# Sheet1.net
KiCad netlist of a schematic drawn in Altium Designer
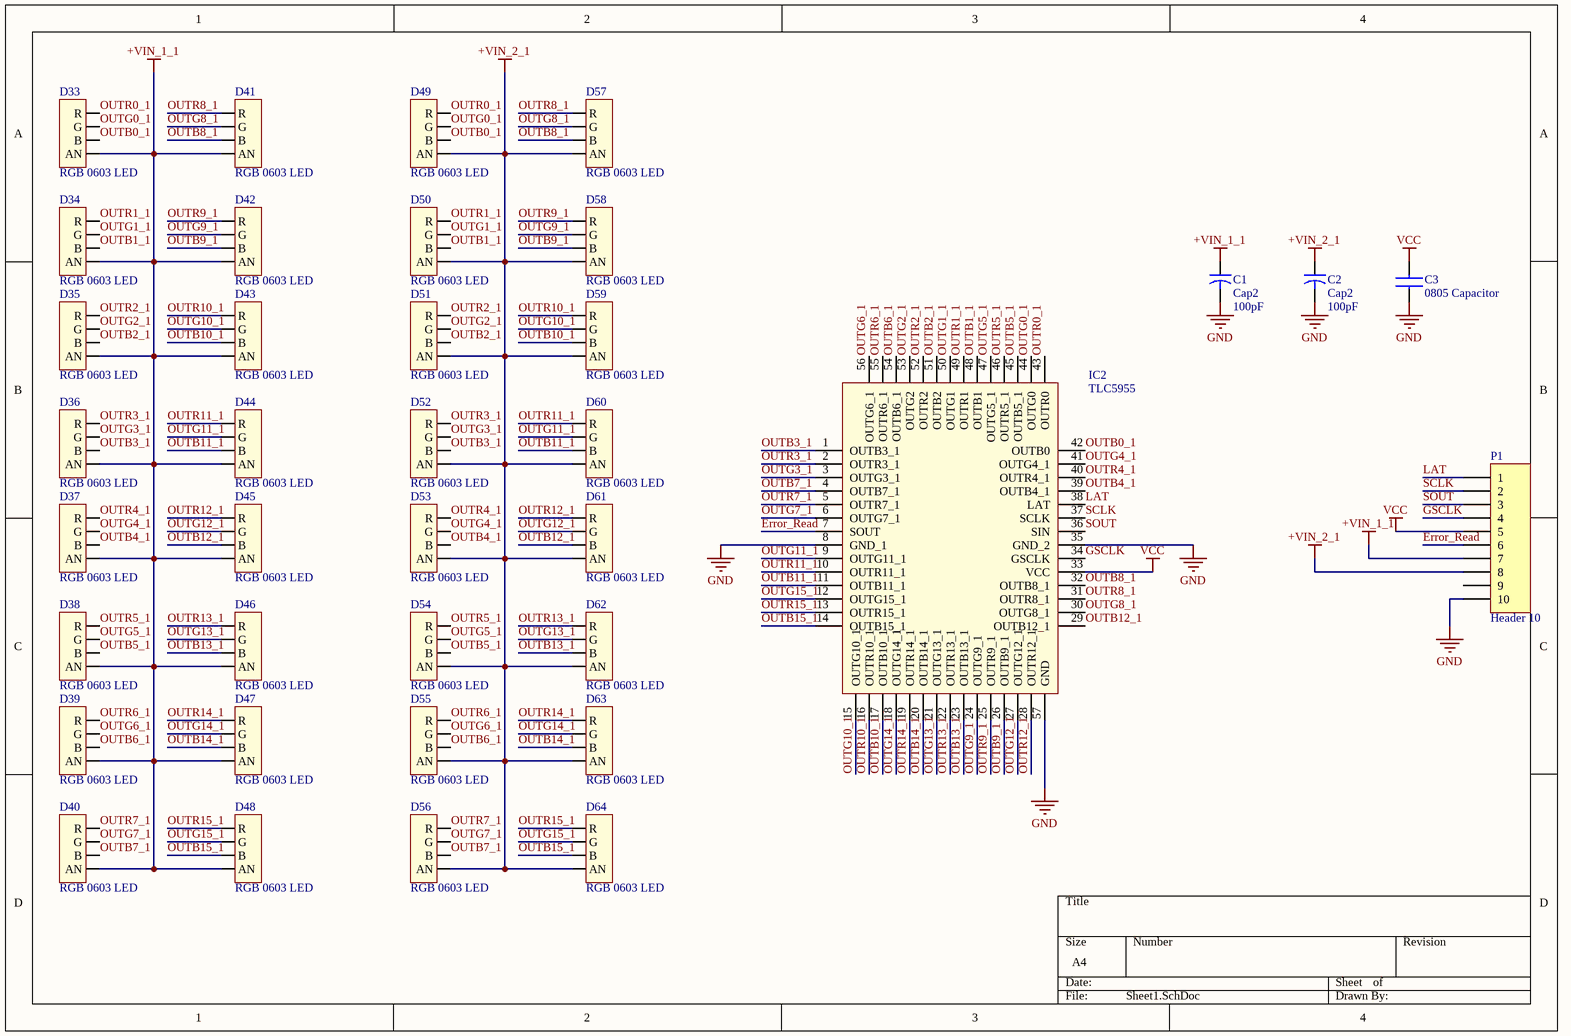
[diagram p0: Sheet1.SchDoc]

(export (version "E")
  (design (tool "Eeschema 10.0.6"))
  (components
    (comp (ref "C1")
      (value "Cap2")
      (footprint "CAPR5-4X5")
      (description "Capacitor")
      (fields (field (name "ALTIUM_VALUE") "100pF") (field (name "PUBLISHER") "Altium Limited"))
      (libsource (lib "Miscellaneous Devices") (part "Cap2"))
    )
    (comp (ref "C2")
      (value "Cap2")
      (footprint "CAPR5-4X5")
      (description "Capacitor")
      (fields (field (name "ALTIUM_VALUE") "100pF") (field (name "PUBLISHER") "Altium Limited"))
      (libsource (lib "Miscellaneous Devices") (part "Cap2"))
    )
    (comp (ref "C3")
      (value "0805 Capacitor")
      (footprint "0805 Capacitor")
      (libsource (lib "Schlib1") (part "0805 Capacitor"))
    )
    (comp (ref "D33")
      (value "RGB 0603 LED")
      (footprint "RGB LED")
      (libsource (lib "Schlib1") (part "RGB 0603 LED"))
    )
    (comp (ref "D34")
      (value "RGB 0603 LED")
      (footprint "RGB LED")
      (libsource (lib "Schlib1") (part "RGB 0603 LED"))
    )
    (comp (ref "D35")
      (value "RGB 0603 LED")
      (footprint "RGB LED")
      (libsource (lib "Schlib1") (part "RGB 0603 LED"))
    )
    (comp (ref "D36")
      (value "RGB 0603 LED")
      (footprint "RGB LED")
      (libsource (lib "Schlib1") (part "RGB 0603 LED"))
    )
    (comp (ref "D37")
      (value "RGB 0603 LED")
      (footprint "RGB LED")
      (libsource (lib "Schlib1") (part "RGB 0603 LED"))
    )
    (comp (ref "D38")
      (value "RGB 0603 LED")
      (footprint "RGB LED")
      (libsource (lib "Schlib1") (part "RGB 0603 LED"))
    )
    (comp (ref "D39")
      (value "RGB 0603 LED")
      (footprint "RGB LED")
      (libsource (lib "Schlib1") (part "RGB 0603 LED"))
    )
    (comp (ref "D40")
      (value "RGB 0603 LED")
      (footprint "RGB LED")
      (libsource (lib "Schlib1") (part "RGB 0603 LED"))
    )
    (comp (ref "D41")
      (value "RGB 0603 LED")
      (footprint "RGB LED")
      (libsource (lib "") (part "RGB 0603 LED_1"))
    )
    (comp (ref "D42")
      (value "RGB 0603 LED")
      (footprint "RGB LED")
      (libsource (lib "") (part "RGB 0603 LED_1"))
    )
    (comp (ref "D43")
      (value "RGB 0603 LED")
      (footprint "RGB LED")
      (libsource (lib "") (part "RGB 0603 LED_1"))
    )
    (comp (ref "D44")
      (value "RGB 0603 LED")
      (footprint "RGB LED")
      (libsource (lib "") (part "RGB 0603 LED_1"))
    )
    (comp (ref "D45")
      (value "RGB 0603 LED")
      (footprint "RGB LED")
      (libsource (lib "") (part "RGB 0603 LED_1"))
    )
    (comp (ref "D46")
      (value "RGB 0603 LED")
      (footprint "RGB LED")
      (libsource (lib "") (part "RGB 0603 LED_1"))
    )
    (comp (ref "D47")
      (value "RGB 0603 LED")
      (footprint "RGB LED")
      (libsource (lib "") (part "RGB 0603 LED_1"))
    )
    (comp (ref "D48")
      (value "RGB 0603 LED")
      (footprint "RGB LED")
      (libsource (lib "") (part "RGB 0603 LED_1"))
    )
    (comp (ref "D49")
      (value "RGB 0603 LED")
      (footprint "RGB LED")
      (libsource (lib "Schlib1") (part "RGB 0603 LED"))
    )
    (comp (ref "D50")
      (value "RGB 0603 LED")
      (footprint "RGB LED")
      (libsource (lib "Schlib1") (part "RGB 0603 LED"))
    )
    (comp (ref "D51")
      (value "RGB 0603 LED")
      (footprint "RGB LED")
      (libsource (lib "Schlib1") (part "RGB 0603 LED"))
    )
    (comp (ref "D52")
      (value "RGB 0603 LED")
      (footprint "RGB LED")
      (libsource (lib "Schlib1") (part "RGB 0603 LED"))
    )
    (comp (ref "D53")
      (value "RGB 0603 LED")
      (footprint "RGB LED")
      (libsource (lib "Schlib1") (part "RGB 0603 LED"))
    )
    (comp (ref "D54")
      (value "RGB 0603 LED")
      (footprint "RGB LED")
      (libsource (lib "Schlib1") (part "RGB 0603 LED"))
    )
    (comp (ref "D55")
      (value "RGB 0603 LED")
      (footprint "RGB LED")
      (libsource (lib "Schlib1") (part "RGB 0603 LED"))
    )
    (comp (ref "D56")
      (value "RGB 0603 LED")
      (footprint "RGB LED")
      (libsource (lib "Schlib1") (part "RGB 0603 LED"))
    )
    (comp (ref "D57")
      (value "RGB 0603 LED")
      (footprint "RGB LED")
      (libsource (lib "") (part "RGB 0603 LED_1"))
    )
    (comp (ref "D58")
      (value "RGB 0603 LED")
      (footprint "RGB LED")
      (libsource (lib "") (part "RGB 0603 LED_1"))
    )
    (comp (ref "D59")
      (value "RGB 0603 LED")
      (footprint "RGB LED")
      (libsource (lib "") (part "RGB 0603 LED_1"))
    )
    (comp (ref "D60")
      (value "RGB 0603 LED")
      (footprint "RGB LED")
      (libsource (lib "") (part "RGB 0603 LED_1"))
    )
    (comp (ref "D61")
      (value "RGB 0603 LED")
      (footprint "RGB LED")
      (libsource (lib "") (part "RGB 0603 LED_1"))
    )
    (comp (ref "D62")
      (value "RGB 0603 LED")
      (footprint "RGB LED")
      (libsource (lib "") (part "RGB 0603 LED_1"))
    )
    (comp (ref "D63")
      (value "RGB 0603 LED")
      (footprint "RGB LED")
      (libsource (lib "") (part "RGB 0603 LED_1"))
    )
    (comp (ref "D64")
      (value "RGB 0603 LED")
      (footprint "RGB LED")
      (libsource (lib "") (part "RGB 0603 LED_1"))
    )
    (comp (ref "IC2") (value "TLC5955") (footprint "TLC5955") (libsource (lib "Schlib1") (part "TLC5955")))
    (comp (ref "P1")
      (value "Header 10")
      (footprint "HDR1X10")
      (description "Header, 10-Pin")
      (fields (field (name "PUBLISHER") "Altium Limited"))
      (libsource (lib "Miscellaneous Connectors") (part "Header 10"))
    )
  )
  (nets
    (net (code "1") (name "+VIN_1_1") (class "Default")
      (node (ref "C1") (pin "1") (pinfunction "1_1") (pintype "passive"))
      (node (ref "D33") (pin "4") (pinfunction "AN_4") (pintype "passive"))
      (node (ref "D34") (pin "4") (pinfunction "AN_4") (pintype "passive"))
      (node (ref "D35") (pin "4") (pinfunction "AN_4") (pintype "passive"))
      (node (ref "D36") (pin "4") (pinfunction "AN_4") (pintype "passive"))
      (node (ref "D37") (pin "4") (pinfunction "AN_4") (pintype "passive"))
      (node (ref "D38") (pin "4") (pinfunction "AN_4") (pintype "passive"))
      (node (ref "D39") (pin "4") (pinfunction "AN_4") (pintype "passive"))
      (node (ref "D40") (pin "4") (pinfunction "AN_4") (pintype "passive"))
      (node (ref "D41") (pin "4") (pinfunction "AN_4") (pintype "passive"))
      (node (ref "D42") (pin "4") (pinfunction "AN_4") (pintype "passive"))
      (node (ref "D43") (pin "4") (pinfunction "AN_4") (pintype "passive"))
      (node (ref "D44") (pin "4") (pinfunction "AN_4") (pintype "passive"))
      (node (ref "D45") (pin "4") (pinfunction "AN_4") (pintype "passive"))
      (node (ref "D46") (pin "4") (pinfunction "AN_4") (pintype "passive"))
      (node (ref "D47") (pin "4") (pinfunction "AN_4") (pintype "passive"))
      (node (ref "D48") (pin "4") (pinfunction "AN_4") (pintype "passive"))
      (node (ref "P1") (pin "7") (pinfunction "7_7") (pintype "passive"))
    )
    (net (code "2") (name "+VIN_2_1") (class "Default")
      (node (ref "C2") (pin "1") (pinfunction "1_1") (pintype "passive"))
      (node (ref "D49") (pin "4") (pinfunction "AN_4") (pintype "passive"))
      (node (ref "D50") (pin "4") (pinfunction "AN_4") (pintype "passive"))
      (node (ref "D51") (pin "4") (pinfunction "AN_4") (pintype "passive"))
      (node (ref "D52") (pin "4") (pinfunction "AN_4") (pintype "passive"))
      (node (ref "D53") (pin "4") (pinfunction "AN_4") (pintype "passive"))
      (node (ref "D54") (pin "4") (pinfunction "AN_4") (pintype "passive"))
      (node (ref "D55") (pin "4") (pinfunction "AN_4") (pintype "passive"))
      (node (ref "D56") (pin "4") (pinfunction "AN_4") (pintype "passive"))
      (node (ref "D57") (pin "4") (pinfunction "AN_4") (pintype "passive"))
      (node (ref "D58") (pin "4") (pinfunction "AN_4") (pintype "passive"))
      (node (ref "D59") (pin "4") (pinfunction "AN_4") (pintype "passive"))
      (node (ref "D60") (pin "4") (pinfunction "AN_4") (pintype "passive"))
      (node (ref "D61") (pin "4") (pinfunction "AN_4") (pintype "passive"))
      (node (ref "D62") (pin "4") (pinfunction "AN_4") (pintype "passive"))
      (node (ref "D63") (pin "4") (pinfunction "AN_4") (pintype "passive"))
      (node (ref "D64") (pin "4") (pinfunction "AN_4") (pintype "passive"))
      (node (ref "P1") (pin "8") (pinfunction "8_8") (pintype "passive"))
    )
    (net (code "3") (name "/Error_Read") (class "Default")
      (node (ref "IC2") (pin "7") (pinfunction "SOUT_7") (pintype "passive"))
      (node (ref "P1") (pin "6") (pinfunction "6_6") (pintype "passive"))
    )
    (net (code "4") (name "/GSCLK") (class "Default")
      (node (ref "IC2") (pin "34") (pinfunction "GSCLK_34") (pintype "passive"))
      (node (ref "P1") (pin "4") (pinfunction "4_4") (pintype "passive"))
    )
    (net (code "5") (name "/LAT") (class "Default")
      (node (ref "IC2") (pin "38") (pinfunction "LAT_38") (pintype "passive"))
      (node (ref "P1") (pin "1") (pinfunction "1_1") (pintype "passive"))
    )
    (net (code "6") (name "/OUTB0_1") (class "Default")
      (node (ref "D33") (pin "3") (pinfunction "B_3") (pintype "passive"))
      (node (ref "D49") (pin "3") (pinfunction "B_3") (pintype "passive"))
      (node (ref "IC2") (pin "42") (pinfunction "OUTB0_42") (pintype "passive"))
    )
    (net (code "7") (name "/OUTB1_1") (class "Default")
      (node (ref "D34") (pin "3") (pinfunction "B_3") (pintype "passive"))
      (node (ref "D50") (pin "3") (pinfunction "B_3") (pintype "passive"))
      (node (ref "IC2") (pin "48") (pinfunction "OUTB1_48") (pintype "passive"))
    )
    (net (code "8") (name "/OUTB2_1") (class "Default")
      (node (ref "D35") (pin "3") (pinfunction "B_3") (pintype "passive"))
      (node (ref "D51") (pin "3") (pinfunction "B_3") (pintype "passive"))
      (node (ref "IC2") (pin "51") (pinfunction "OUTB2_51") (pintype "passive"))
    )
    (net (code "9") (name "/OUTB3_1") (class "Default")
      (node (ref "D36") (pin "3") (pinfunction "B_3") (pintype "passive"))
      (node (ref "D52") (pin "3") (pinfunction "B_3") (pintype "passive"))
      (node (ref "IC2") (pin "1") (pinfunction "OUTB3_1_1") (pintype "passive"))
    )
    (net (code "10") (name "/OUTB4_1") (class "Default")
      (node (ref "D37") (pin "3") (pinfunction "B_3") (pintype "passive"))
      (node (ref "D53") (pin "3") (pinfunction "B_3") (pintype "passive"))
      (node (ref "IC2") (pin "39") (pinfunction "OUTB4_1_39") (pintype "passive"))
    )
    (net (code "11") (name "/OUTB5_1") (class "Default")
      (node (ref "D38") (pin "3") (pinfunction "B_3") (pintype "passive"))
      (node (ref "D54") (pin "3") (pinfunction "B_3") (pintype "passive"))
      (node (ref "IC2") (pin "45") (pinfunction "OUTB5_1_45") (pintype "passive"))
    )
    (net (code "12") (name "/OUTB6_1") (class "Default")
      (node (ref "D39") (pin "3") (pinfunction "B_3") (pintype "passive"))
      (node (ref "D55") (pin "3") (pinfunction "B_3") (pintype "passive"))
      (node (ref "IC2") (pin "54") (pinfunction "OUTB6_1_54") (pintype "passive"))
    )
    (net (code "13") (name "/OUTB7_1") (class "Default")
      (node (ref "D40") (pin "3") (pinfunction "B_3") (pintype "passive"))
      (node (ref "D56") (pin "3") (pinfunction "B_3") (pintype "passive"))
      (node (ref "IC2") (pin "4") (pinfunction "OUTB7_1_4") (pintype "passive"))
    )
    (net (code "14") (name "/OUTB8_1") (class "Default")
      (node (ref "D41") (pin "3") (pinfunction "B_3") (pintype "passive"))
      (node (ref "D57") (pin "3") (pinfunction "B_3") (pintype "passive"))
      (node (ref "IC2") (pin "32") (pinfunction "OUTB8_1_32") (pintype "passive"))
    )
    (net (code "15") (name "/OUTB9_1") (class "Default")
      (node (ref "D42") (pin "3") (pinfunction "B_3") (pintype "passive"))
      (node (ref "D58") (pin "3") (pinfunction "B_3") (pintype "passive"))
      (node (ref "IC2") (pin "26") (pinfunction "OUTB9_1_26") (pintype "passive"))
    )
    (net (code "16") (name "/OUTB10_1") (class "Default")
      (node (ref "D43") (pin "3") (pinfunction "B_3") (pintype "passive"))
      (node (ref "D59") (pin "3") (pinfunction "B_3") (pintype "passive"))
      (node (ref "IC2") (pin "17") (pinfunction "OUTB10_1_17") (pintype "passive"))
    )
    (net (code "17") (name "/OUTB11_1") (class "Default")
      (node (ref "D44") (pin "3") (pinfunction "B_3") (pintype "passive"))
      (node (ref "D60") (pin "3") (pinfunction "B_3") (pintype "passive"))
      (node (ref "IC2") (pin "11") (pinfunction "OUTB11_1_11") (pintype "passive"))
    )
    (net (code "18") (name "/OUTB12_1") (class "Default")
      (node (ref "D45") (pin "3") (pinfunction "B_3") (pintype "passive"))
      (node (ref "D61") (pin "3") (pinfunction "B_3") (pintype "passive"))
      (node (ref "IC2") (pin "29") (pinfunction "OUTB12_1_29") (pintype "passive"))
    )
    (net (code "19") (name "/OUTB13_1") (class "Default")
      (node (ref "D46") (pin "3") (pinfunction "B_3") (pintype "passive"))
      (node (ref "D62") (pin "3") (pinfunction "B_3") (pintype "passive"))
      (node (ref "IC2") (pin "23") (pinfunction "OUTB13_1_23") (pintype "passive"))
    )
    (net (code "20") (name "/OUTB14_1") (class "Default")
      (node (ref "D47") (pin "3") (pinfunction "B_3") (pintype "passive"))
      (node (ref "D63") (pin "3") (pinfunction "B_3") (pintype "passive"))
      (node (ref "IC2") (pin "20") (pinfunction "OUTB14_1_20") (pintype "passive"))
    )
    (net (code "21") (name "/OUTB15_1") (class "Default")
      (node (ref "D48") (pin "3") (pinfunction "B_3") (pintype "passive"))
      (node (ref "D64") (pin "3") (pinfunction "B_3") (pintype "passive"))
      (node (ref "IC2") (pin "14") (pinfunction "OUTB15_1_14") (pintype "passive"))
    )
    (net (code "22") (name "/OUTG0_1") (class "Default")
      (node (ref "D33") (pin "2") (pinfunction "G_2") (pintype "passive"))
      (node (ref "D49") (pin "2") (pinfunction "G_2") (pintype "passive"))
      (node (ref "IC2") (pin "44") (pinfunction "OUTG0_44") (pintype "passive"))
    )
    (net (code "23") (name "/OUTG1_1") (class "Default")
      (node (ref "D34") (pin "2") (pinfunction "G_2") (pintype "passive"))
      (node (ref "D50") (pin "2") (pinfunction "G_2") (pintype "passive"))
      (node (ref "IC2") (pin "50") (pinfunction "OUTG1_50") (pintype "passive"))
    )
    (net (code "24") (name "/OUTG2_1") (class "Default")
      (node (ref "D35") (pin "2") (pinfunction "G_2") (pintype "passive"))
      (node (ref "D51") (pin "2") (pinfunction "G_2") (pintype "passive"))
      (node (ref "IC2") (pin "53") (pinfunction "OUTG2_53") (pintype "passive"))
    )
    (net (code "25") (name "/OUTG3_1") (class "Default")
      (node (ref "D36") (pin "2") (pinfunction "G_2") (pintype "passive"))
      (node (ref "D52") (pin "2") (pinfunction "G_2") (pintype "passive"))
      (node (ref "IC2") (pin "3") (pinfunction "OUTG3_1_3") (pintype "passive"))
    )
    (net (code "26") (name "/OUTG4_1") (class "Default")
      (node (ref "D37") (pin "2") (pinfunction "G_2") (pintype "passive"))
      (node (ref "D53") (pin "2") (pinfunction "G_2") (pintype "passive"))
      (node (ref "IC2") (pin "41") (pinfunction "OUTG4_1_41") (pintype "passive"))
    )
    (net (code "27") (name "/OUTG5_1") (class "Default")
      (node (ref "D38") (pin "2") (pinfunction "G_2") (pintype "passive"))
      (node (ref "D54") (pin "2") (pinfunction "G_2") (pintype "passive"))
      (node (ref "IC2") (pin "47") (pinfunction "OUTG5_1_47") (pintype "passive"))
    )
    (net (code "28") (name "/OUTG6_1") (class "Default")
      (node (ref "D39") (pin "2") (pinfunction "G_2") (pintype "passive"))
      (node (ref "D55") (pin "2") (pinfunction "G_2") (pintype "passive"))
      (node (ref "IC2") (pin "56") (pinfunction "OUTG6_1_56") (pintype "passive"))
    )
    (net (code "29") (name "/OUTG7_1") (class "Default")
      (node (ref "D40") (pin "2") (pinfunction "G_2") (pintype "passive"))
      (node (ref "D56") (pin "2") (pinfunction "G_2") (pintype "passive"))
      (node (ref "IC2") (pin "6") (pinfunction "OUTG7_1_6") (pintype "passive"))
    )
    (net (code "30") (name "/OUTG8_1") (class "Default")
      (node (ref "D41") (pin "2") (pinfunction "G_2") (pintype "passive"))
      (node (ref "D57") (pin "2") (pinfunction "G_2") (pintype "passive"))
      (node (ref "IC2") (pin "30") (pinfunction "OUTG8_1_30") (pintype "passive"))
    )
    (net (code "31") (name "/OUTG9_1") (class "Default")
      (node (ref "D42") (pin "2") (pinfunction "G_2") (pintype "passive"))
      (node (ref "D58") (pin "2") (pinfunction "G_2") (pintype "passive"))
      (node (ref "IC2") (pin "24") (pinfunction "OUTG9_1_24") (pintype "passive"))
    )
    (net (code "32") (name "/OUTG10_1") (class "Default")
      (node (ref "D43") (pin "2") (pinfunction "G_2") (pintype "passive"))
      (node (ref "D59") (pin "2") (pinfunction "G_2") (pintype "passive"))
      (node (ref "IC2") (pin "15") (pinfunction "OUTG10_1_15") (pintype "passive"))
    )
    (net (code "33") (name "/OUTG11_1") (class "Default")
      (node (ref "D44") (pin "2") (pinfunction "G_2") (pintype "passive"))
      (node (ref "D60") (pin "2") (pinfunction "G_2") (pintype "passive"))
      (node (ref "IC2") (pin "9") (pinfunction "OUTG11_1_9") (pintype "passive"))
    )
    (net (code "34") (name "/OUTG12_1") (class "Default")
      (node (ref "D45") (pin "2") (pinfunction "G_2") (pintype "passive"))
      (node (ref "D61") (pin "2") (pinfunction "G_2") (pintype "passive"))
      (node (ref "IC2") (pin "27") (pinfunction "OUTG12_1_27") (pintype "passive"))
    )
    (net (code "35") (name "/OUTG13_1") (class "Default")
      (node (ref "D46") (pin "2") (pinfunction "G_2") (pintype "passive"))
      (node (ref "D62") (pin "2") (pinfunction "G_2") (pintype "passive"))
      (node (ref "IC2") (pin "21") (pinfunction "OUTG13_1_21") (pintype "passive"))
    )
    (net (code "36") (name "/OUTG14_1") (class "Default")
      (node (ref "D47") (pin "2") (pinfunction "G_2") (pintype "passive"))
      (node (ref "D63") (pin "2") (pinfunction "G_2") (pintype "passive"))
      (node (ref "IC2") (pin "18") (pinfunction "OUTG14_1_18") (pintype "passive"))
    )
    (net (code "37") (name "/OUTG15_1") (class "Default")
      (node (ref "D48") (pin "2") (pinfunction "G_2") (pintype "passive"))
      (node (ref "D64") (pin "2") (pinfunction "G_2") (pintype "passive"))
      (node (ref "IC2") (pin "12") (pinfunction "OUTG15_1_12") (pintype "passive"))
    )
    (net (code "38") (name "/OUTR0_1") (class "Default")
      (node (ref "D33") (pin "1") (pinfunction "R_1") (pintype "passive"))
      (node (ref "D49") (pin "1") (pinfunction "R_1") (pintype "passive"))
      (node (ref "IC2") (pin "43") (pinfunction "OUTR0_43") (pintype "passive"))
    )
    (net (code "39") (name "/OUTR1_1") (class "Default")
      (node (ref "D34") (pin "1") (pinfunction "R_1") (pintype "passive"))
      (node (ref "D50") (pin "1") (pinfunction "R_1") (pintype "passive"))
      (node (ref "IC2") (pin "49") (pinfunction "OUTR1_49") (pintype "passive"))
    )
    (net (code "40") (name "/OUTR2_1") (class "Default")
      (node (ref "D35") (pin "1") (pinfunction "R_1") (pintype "passive"))
      (node (ref "D51") (pin "1") (pinfunction "R_1") (pintype "passive"))
      (node (ref "IC2") (pin "52") (pinfunction "OUTR2_52") (pintype "passive"))
    )
    (net (code "41") (name "/OUTR3_1") (class "Default")
      (node (ref "D36") (pin "1") (pinfunction "R_1") (pintype "passive"))
      (node (ref "D52") (pin "1") (pinfunction "R_1") (pintype "passive"))
      (node (ref "IC2") (pin "2") (pinfunction "OUTR3_1_2") (pintype "passive"))
    )
    (net (code "42") (name "/OUTR4_1") (class "Default")
      (node (ref "D37") (pin "1") (pinfunction "R_1") (pintype "passive"))
      (node (ref "D53") (pin "1") (pinfunction "R_1") (pintype "passive"))
      (node (ref "IC2") (pin "40") (pinfunction "OUTR4_1_40") (pintype "passive"))
    )
    (net (code "43") (name "/OUTR5_1") (class "Default")
      (node (ref "D38") (pin "1") (pinfunction "R_1") (pintype "passive"))
      (node (ref "D54") (pin "1") (pinfunction "R_1") (pintype "passive"))
      (node (ref "IC2") (pin "46") (pinfunction "OUTR5_1_46") (pintype "passive"))
    )
    (net (code "44") (name "/OUTR6_1") (class "Default")
      (node (ref "D39") (pin "1") (pinfunction "R_1") (pintype "passive"))
      (node (ref "D55") (pin "1") (pinfunction "R_1") (pintype "passive"))
      (node (ref "IC2") (pin "55") (pinfunction "OUTR6_1_55") (pintype "passive"))
    )
    (net (code "45") (name "/OUTR7_1") (class "Default")
      (node (ref "D40") (pin "1") (pinfunction "R_1") (pintype "passive"))
      (node (ref "D56") (pin "1") (pinfunction "R_1") (pintype "passive"))
      (node (ref "IC2") (pin "5") (pinfunction "OUTR7_1_5") (pintype "passive"))
    )
    (net (code "46") (name "/OUTR8_1") (class "Default")
      (node (ref "D41") (pin "1") (pinfunction "R_1") (pintype "passive"))
      (node (ref "D57") (pin "1") (pinfunction "R_1") (pintype "passive"))
      (node (ref "IC2") (pin "31") (pinfunction "OUTR8_1_31") (pintype "passive"))
    )
    (net (code "47") (name "/OUTR9_1") (class "Default")
      (node (ref "D42") (pin "1") (pinfunction "R_1") (pintype "passive"))
      (node (ref "D58") (pin "1") (pinfunction "R_1") (pintype "passive"))
      (node (ref "IC2") (pin "25") (pinfunction "OUTR9_1_25") (pintype "passive"))
    )
    (net (code "48") (name "/OUTR10_1") (class "Default")
      (node (ref "D43") (pin "1") (pinfunction "R_1") (pintype "passive"))
      (node (ref "D59") (pin "1") (pinfunction "R_1") (pintype "passive"))
      (node (ref "IC2") (pin "16") (pinfunction "OUTR10_1_16") (pintype "passive"))
    )
    (net (code "49") (name "/OUTR11_1") (class "Default")
      (node (ref "D44") (pin "1") (pinfunction "R_1") (pintype "passive"))
      (node (ref "D60") (pin "1") (pinfunction "R_1") (pintype "passive"))
      (node (ref "IC2") (pin "10") (pinfunction "OUTR11_1_10") (pintype "passive"))
    )
    (net (code "50") (name "/OUTR12_1") (class "Default")
      (node (ref "D45") (pin "1") (pinfunction "R_1") (pintype "passive"))
      (node (ref "D61") (pin "1") (pinfunction "R_1") (pintype "passive"))
      (node (ref "IC2") (pin "28") (pinfunction "OUTR12_1_28") (pintype "passive"))
    )
    (net (code "51") (name "/OUTR13_1") (class "Default")
      (node (ref "D46") (pin "1") (pinfunction "R_1") (pintype "passive"))
      (node (ref "D62") (pin "1") (pinfunction "R_1") (pintype "passive"))
      (node (ref "IC2") (pin "22") (pinfunction "OUTR13_1_22") (pintype "passive"))
    )
    (net (code "52") (name "/OUTR14_1") (class "Default")
      (node (ref "D47") (pin "1") (pinfunction "R_1") (pintype "passive"))
      (node (ref "D63") (pin "1") (pinfunction "R_1") (pintype "passive"))
      (node (ref "IC2") (pin "19") (pinfunction "OUTR14_1_19") (pintype "passive"))
    )
    (net (code "53") (name "/OUTR15_1") (class "Default")
      (node (ref "D48") (pin "1") (pinfunction "R_1") (pintype "passive"))
      (node (ref "D64") (pin "1") (pinfunction "R_1") (pintype "passive"))
      (node (ref "IC2") (pin "13") (pinfunction "OUTR15_1_13") (pintype "passive"))
    )
    (net (code "54") (name "/SCLK") (class "Default")
      (node (ref "IC2") (pin "37") (pinfunction "SCLK_37") (pintype "passive"))
      (node (ref "P1") (pin "2") (pinfunction "2_2") (pintype "passive"))
    )
    (net (code "55") (name "/SOUT") (class "Default")
      (node (ref "IC2") (pin "36") (pinfunction "SIN_36") (pintype "passive"))
      (node (ref "P1") (pin "3") (pinfunction "3_3") (pintype "passive"))
    )
    (net (code "56") (name "GND") (class "Default")
      (node (ref "C1") (pin "2") (pinfunction "2_2") (pintype "passive"))
      (node (ref "C2") (pin "2") (pinfunction "2_2") (pintype "passive"))
      (node (ref "C3") (pin "1") (pinfunction "1_1") (pintype "passive"))
      (node (ref "IC2") (pin "35") (pinfunction "GND_2_35") (pintype "passive"))
      (node (ref "IC2") (pin "57") (pinfunction "GND_57") (pintype "passive"))
      (node (ref "IC2") (pin "8") (pinfunction "GND_1_8") (pintype "passive"))
      (node (ref "P1") (pin "10") (pinfunction "10_10") (pintype "passive"))
    )
    (net (code "57") (name "VCC") (class "Default")
      (node (ref "C3") (pin "2") (pinfunction "2_2") (pintype "passive"))
      (node (ref "IC2") (pin "33") (pinfunction "VCC_33") (pintype "passive"))
      (node (ref "P1") (pin "5") (pinfunction "5_5") (pintype "passive"))
    )
    (net (code "58") (name "unconnected-(P1-Pad9)") (class "Default")
      (node (ref "P1") (pin "9") (pinfunction "9_9") (pintype "passive"))
    )
  )
)
